# various.net
KiCad netlist of a schematic drawn in EAGLE
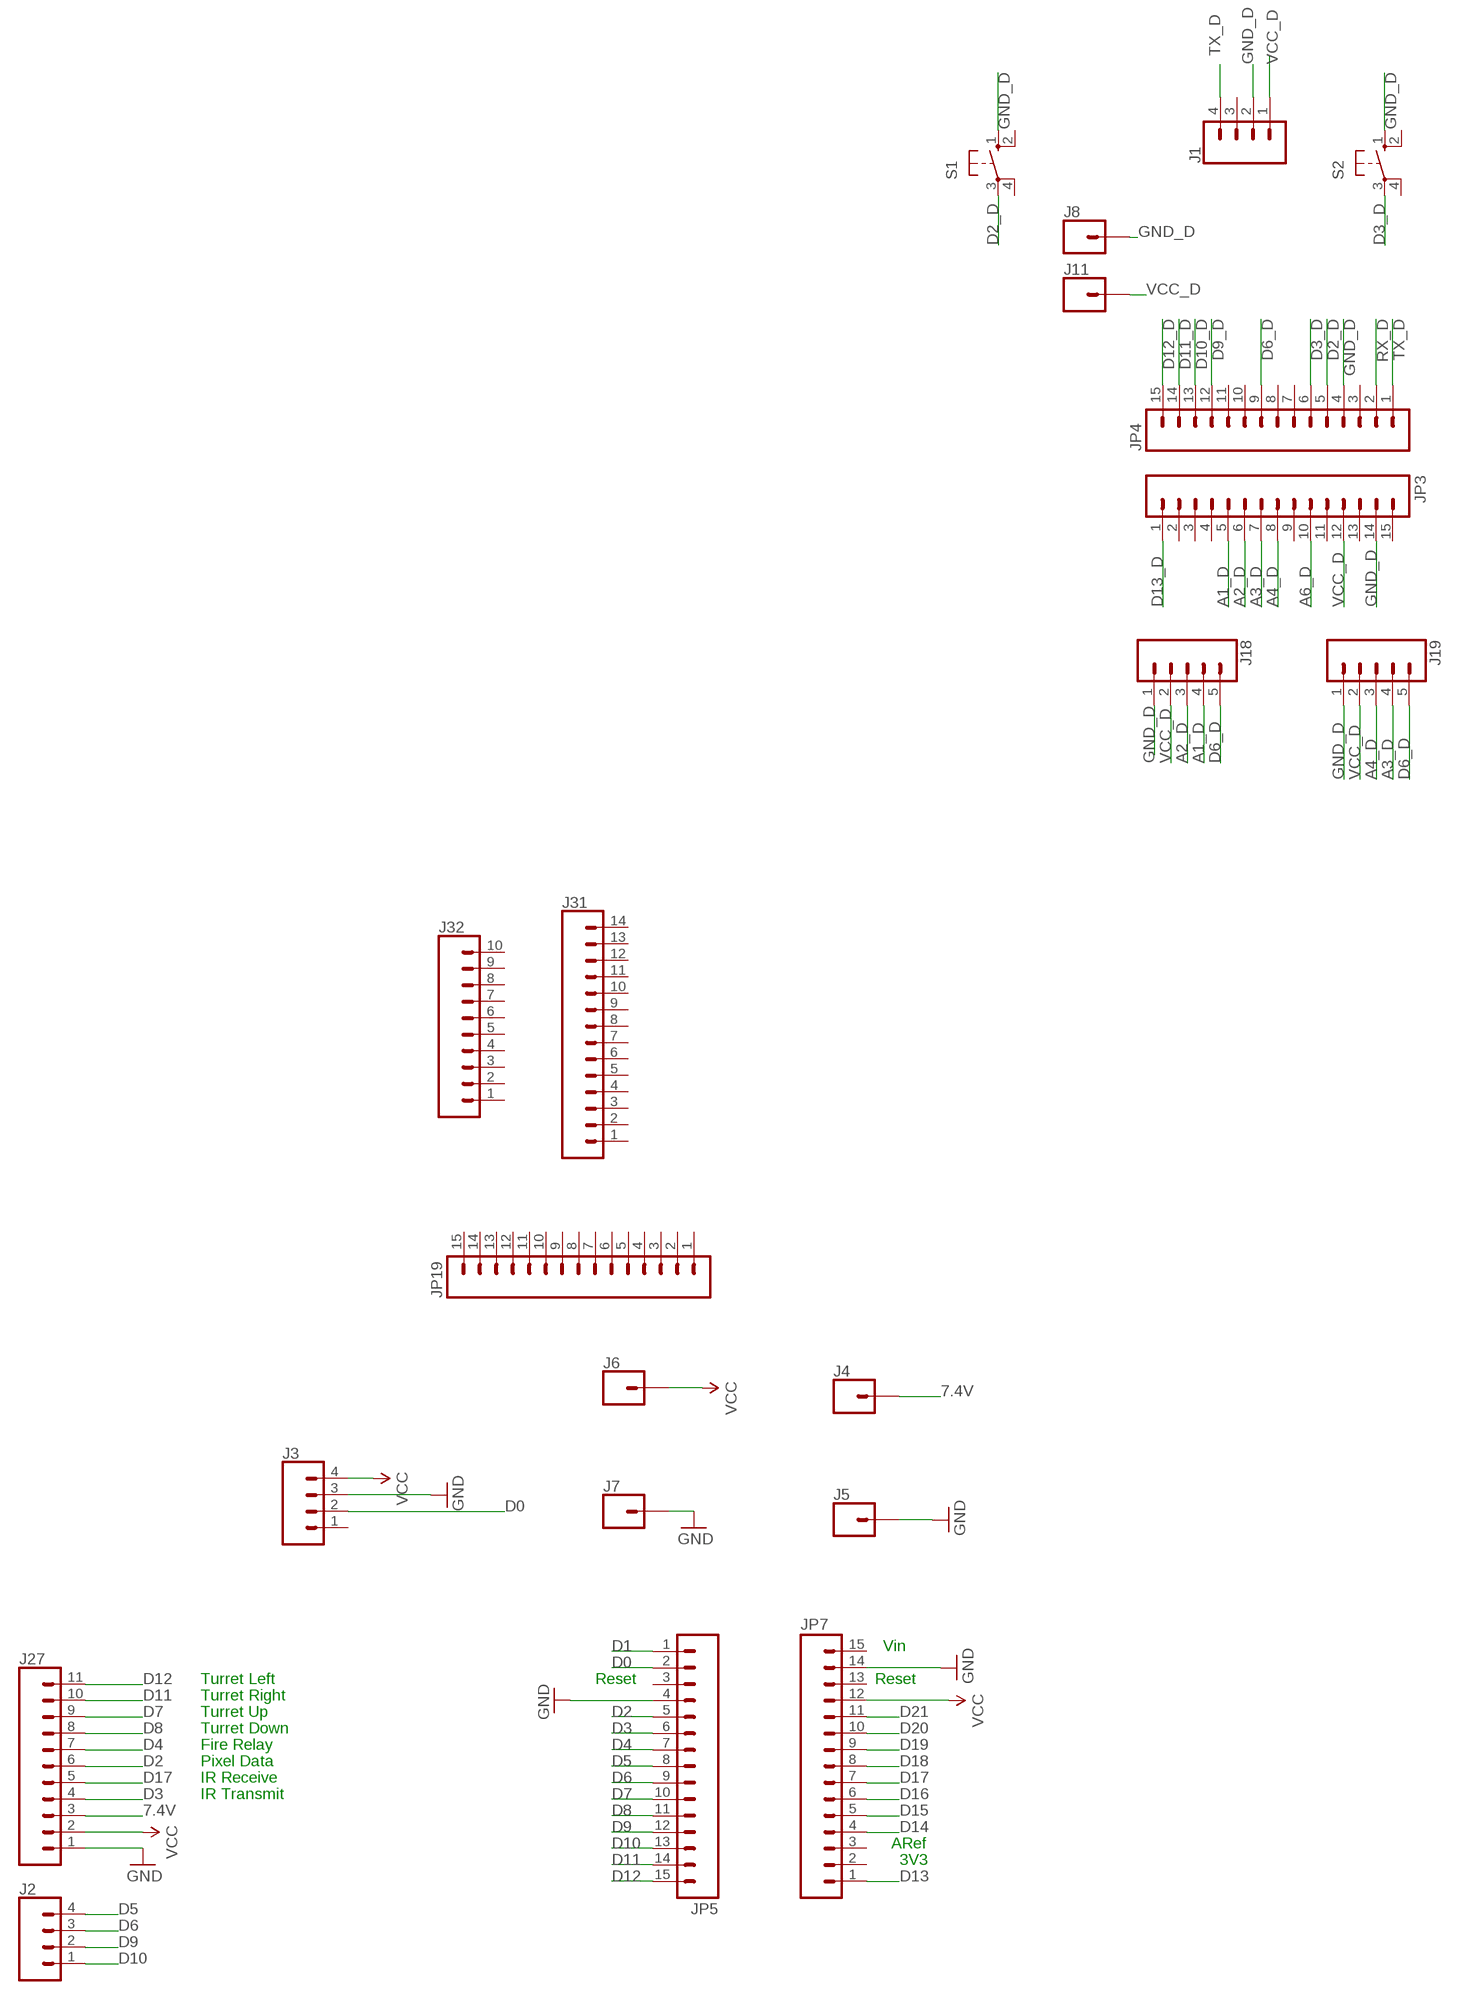
[diagram p0: schematic, sheet 1]

(export (version "E")
  (design (tool "Eeschema 10.0.6"))
  (components
    (comp (ref "J1")
      (value "CONN_04")
      (footprint "eagle-import:1X04")
      (libsource (lib "eagle-import") (part "SparkFun-Connectors_513_CONN_04"))
    )
    (comp (ref "J2")
      (value "CONN_04")
      (footprint "eagle-import:1X04")
      (libsource (lib "eagle-import") (part "CONN_04"))
    )
    (comp (ref "J3")
      (value "CONN_04")
      (footprint "eagle-import:1X04")
      (libsource (lib "eagle-import") (part "CONN_04"))
    )
    (comp (ref "J4")
      (value "CONN_01")
      (footprint "eagle-import:1X01")
      (libsource (lib "eagle-import") (part "CONN_01"))
    )
    (comp (ref "J5")
      (value "CONN_01")
      (footprint "eagle-import:1X01")
      (libsource (lib "eagle-import") (part "CONN_01"))
    )
    (comp (ref "J6")
      (value "CONN_01")
      (footprint "eagle-import:1X01")
      (libsource (lib "eagle-import") (part "CONN_01"))
    )
    (comp (ref "J7")
      (value "CONN_01")
      (footprint "eagle-import:1X01")
      (libsource (lib "eagle-import") (part "CONN_01"))
    )
    (comp (ref "J8")
      (value "CONN_01")
      (footprint "eagle-import:1X01")
      (libsource (lib "eagle-import") (part "CONN_01"))
    )
    (comp (ref "J11")
      (value "CONN_01")
      (footprint "eagle-import:1X01")
      (libsource (lib "eagle-import") (part "CONN_01"))
    )
    (comp (ref "J18")
      (value "CONN_05")
      (footprint "eagle-import:1X05")
      (libsource (lib "eagle-import") (part "CONN_05"))
    )
    (comp (ref "J19")
      (value "CONN_05")
      (footprint "eagle-import:1X05")
      (libsource (lib "eagle-import") (part "CONN_05"))
    )
    (comp (ref "J27")
      (value "CONN_11")
      (footprint "eagle-import:1X11")
      (libsource (lib "eagle-import") (part "CONN_11"))
    )
    (comp (ref "J31")
      (value "CONN_14")
      (footprint "eagle-import:1X14")
      (libsource (lib "eagle-import") (part "CONN_14"))
    )
    (comp (ref "J32")
      (value "CONN_10\"")
      (footprint "eagle-import:1X10")
      (libsource (lib "eagle-import") (part "CONN_10{dblquote}"))
    )
    (comp (ref "JP3")
      (value "M15")
      (footprint "eagle-import:1X15")
      (libsource (lib "eagle-import") (part "M15"))
    )
    (comp (ref "JP4")
      (value "M15")
      (footprint "eagle-import:1X15")
      (libsource (lib "eagle-import") (part "M15"))
    )
    (comp (ref "JP5")
      (value "M15")
      (footprint "eagle-import:1X15")
      (libsource (lib "eagle-import") (part "M15"))
    )
    (comp (ref "JP7")
      (value "M15")
      (footprint "eagle-import:1X15")
      (libsource (lib "eagle-import") (part "M15"))
    )
    (comp (ref "JP19")
      (value "M15")
      (footprint "eagle-import:1X15")
      (libsource (lib "eagle-import") (part "M15"))
    )
    (comp (ref "S1")
      (value "40-XX")
      (footprint "eagle-import:B3F-40XX")
      (fields (field (name "MF") "OMRON COMPONENTS USA") (field (name "MPN") "B3F-4000"))
      (libsource (lib "eagle-import") (part "40-XX"))
    )
    (comp (ref "S2")
      (value "40-XX")
      (footprint "eagle-import:B3F-40XX")
      (fields (field (name "MF") "OMRON COMPONENTS USA") (field (name "MPN") "B3F-4000"))
      (libsource (lib "eagle-import") (part "40-XX"))
    )
  )
  (nets
    (net (code "1") (name "/7.4V") (class "Default")
      (node (ref "J27") (pin "3") (pinfunction "3_3") (pintype "passive"))
      (node (ref "J4") (pin "1") (pinfunction "1_1") (pintype "passive"))
    )
    (net (code "2") (name "/A1_D") (class "Default")
      (node (ref "J18") (pin "4") (pinfunction "4_4") (pintype "passive"))
      (node (ref "JP3") (pin "5") (pinfunction "5_5") (pintype "passive"))
    )
    (net (code "3") (name "/A2_D") (class "Default")
      (node (ref "J18") (pin "3") (pinfunction "3_3") (pintype "passive"))
      (node (ref "JP3") (pin "6") (pinfunction "6_6") (pintype "passive"))
    )
    (net (code "4") (name "/A3_D") (class "Default")
      (node (ref "J19") (pin "4") (pinfunction "4_4") (pintype "passive"))
      (node (ref "JP3") (pin "7") (pinfunction "7_7") (pintype "passive"))
    )
    (net (code "5") (name "/A4_D") (class "Default")
      (node (ref "J19") (pin "3") (pinfunction "3_3") (pintype "passive"))
      (node (ref "JP3") (pin "8") (pinfunction "8_8") (pintype "passive"))
    )
    (net (code "6") (name "/A6_D") (class "Default")
      (node (ref "JP3") (pin "10") (pinfunction "10_10") (pintype "passive"))
    )
    (net (code "7") (name "/D0") (class "Default")
      (node (ref "J3") (pin "2") (pinfunction "2_2") (pintype "passive"))
      (node (ref "JP5") (pin "2") (pinfunction "2_2") (pintype "passive"))
    )
    (net (code "8") (name "/D1") (class "Default")
      (node (ref "JP5") (pin "1") (pinfunction "1_1") (pintype "passive"))
    )
    (net (code "9") (name "/D2") (class "Default")
      (node (ref "J27") (pin "6") (pinfunction "6_6") (pintype "passive"))
      (node (ref "JP5") (pin "5") (pinfunction "5_5") (pintype "passive"))
    )
    (net (code "10") (name "/D2_D") (class "Default")
      (node (ref "JP4") (pin "5") (pinfunction "5_5") (pintype "passive"))
      (node (ref "S1") (pin "3") (pinfunction "P_3") (pintype "passive"))
    )
    (net (code "11") (name "/D3") (class "Default")
      (node (ref "J27") (pin "4") (pinfunction "4_4") (pintype "passive"))
      (node (ref "JP5") (pin "6") (pinfunction "6_6") (pintype "passive"))
    )
    (net (code "12") (name "/D3_D") (class "Default")
      (node (ref "JP4") (pin "6") (pinfunction "6_6") (pintype "passive"))
      (node (ref "S2") (pin "3") (pinfunction "P_3") (pintype "passive"))
    )
    (net (code "13") (name "/D4") (class "Default")
      (node (ref "J27") (pin "7") (pinfunction "7_7") (pintype "passive"))
      (node (ref "JP5") (pin "7") (pinfunction "7_7") (pintype "passive"))
    )
    (net (code "14") (name "/D5") (class "Default")
      (node (ref "J2") (pin "4") (pinfunction "4_4") (pintype "passive"))
      (node (ref "JP5") (pin "8") (pinfunction "8_8") (pintype "passive"))
    )
    (net (code "15") (name "/D6") (class "Default")
      (node (ref "J2") (pin "3") (pinfunction "3_3") (pintype "passive"))
      (node (ref "JP5") (pin "9") (pinfunction "9_9") (pintype "passive"))
    )
    (net (code "16") (name "/D6_D") (class "Default")
      (node (ref "J18") (pin "5") (pinfunction "5_5") (pintype "passive"))
      (node (ref "J19") (pin "5") (pinfunction "5_5") (pintype "passive"))
      (node (ref "JP4") (pin "9") (pinfunction "9_9") (pintype "passive"))
    )
    (net (code "17") (name "/D7") (class "Default")
      (node (ref "J27") (pin "9") (pinfunction "9_9") (pintype "passive"))
      (node (ref "JP5") (pin "10") (pinfunction "10_10") (pintype "passive"))
    )
    (net (code "18") (name "/D8") (class "Default")
      (node (ref "J27") (pin "8") (pinfunction "8_8") (pintype "passive"))
      (node (ref "JP5") (pin "11") (pinfunction "11_11") (pintype "passive"))
    )
    (net (code "19") (name "/D9") (class "Default")
      (node (ref "J2") (pin "2") (pinfunction "2_2") (pintype "passive"))
      (node (ref "JP5") (pin "12") (pinfunction "12_12") (pintype "passive"))
    )
    (net (code "20") (name "/D9_D") (class "Default")
      (node (ref "JP4") (pin "12") (pinfunction "12_12") (pintype "passive"))
    )
    (net (code "21") (name "/D10") (class "Default")
      (node (ref "J2") (pin "1") (pinfunction "1_1") (pintype "passive"))
      (node (ref "JP5") (pin "13") (pinfunction "13_13") (pintype "passive"))
    )
    (net (code "22") (name "/D10_D") (class "Default")
      (node (ref "JP4") (pin "13") (pinfunction "13_13") (pintype "passive"))
    )
    (net (code "23") (name "/D11") (class "Default")
      (node (ref "J27") (pin "10") (pinfunction "10_10") (pintype "passive"))
      (node (ref "JP5") (pin "14") (pinfunction "14_14") (pintype "passive"))
    )
    (net (code "24") (name "/D11_D") (class "Default")
      (node (ref "JP4") (pin "14") (pinfunction "14_14") (pintype "passive"))
    )
    (net (code "25") (name "/D12") (class "Default")
      (node (ref "J27") (pin "11") (pinfunction "11_11") (pintype "passive"))
      (node (ref "JP5") (pin "15") (pinfunction "15_15") (pintype "passive"))
    )
    (net (code "26") (name "/D12_D") (class "Default")
      (node (ref "JP4") (pin "15") (pinfunction "15_15") (pintype "passive"))
    )
    (net (code "27") (name "/D13") (class "Default")
      (node (ref "JP7") (pin "1") (pinfunction "1_1") (pintype "passive"))
    )
    (net (code "28") (name "/D13_D") (class "Default")
      (node (ref "JP3") (pin "1") (pinfunction "1_1") (pintype "passive"))
    )
    (net (code "29") (name "/D14") (class "Default")
      (node (ref "JP7") (pin "4") (pinfunction "4_4") (pintype "passive"))
    )
    (net (code "30") (name "/D15") (class "Default")
      (node (ref "JP7") (pin "5") (pinfunction "5_5") (pintype "passive"))
    )
    (net (code "31") (name "/D16") (class "Default")
      (node (ref "JP7") (pin "6") (pinfunction "6_6") (pintype "passive"))
    )
    (net (code "32") (name "/D17") (class "Default")
      (node (ref "J27") (pin "5") (pinfunction "5_5") (pintype "passive"))
      (node (ref "JP7") (pin "7") (pinfunction "7_7") (pintype "passive"))
    )
    (net (code "33") (name "/D18") (class "Default")
      (node (ref "JP7") (pin "8") (pinfunction "8_8") (pintype "passive"))
    )
    (net (code "34") (name "/D19") (class "Default")
      (node (ref "JP7") (pin "9") (pinfunction "9_9") (pintype "passive"))
    )
    (net (code "35") (name "/D20") (class "Default")
      (node (ref "JP7") (pin "10") (pinfunction "10_10") (pintype "passive"))
    )
    (net (code "36") (name "/D21") (class "Default")
      (node (ref "JP7") (pin "11") (pinfunction "11_11") (pintype "passive"))
    )
    (net (code "37") (name "/GND_D") (class "Default")
      (node (ref "J1") (pin "2") (pinfunction "2_2") (pintype "passive"))
      (node (ref "J18") (pin "1") (pinfunction "1_1") (pintype "passive"))
      (node (ref "J19") (pin "1") (pinfunction "1_1") (pintype "passive"))
      (node (ref "J8") (pin "1") (pinfunction "1_1") (pintype "passive"))
      (node (ref "JP3") (pin "14") (pinfunction "14_14") (pintype "passive"))
      (node (ref "JP4") (pin "4") (pinfunction "4_4") (pintype "passive"))
      (node (ref "S1") (pin "1") (pinfunction "S_1") (pintype "passive"))
      (node (ref "S2") (pin "1") (pinfunction "S_1") (pintype "passive"))
    )
    (net (code "38") (name "/RX_D") (class "Default")
      (node (ref "JP4") (pin "2") (pinfunction "2_2") (pintype "passive"))
    )
    (net (code "39") (name "/TX_D") (class "Default")
      (node (ref "J1") (pin "4") (pinfunction "4_4") (pintype "passive"))
      (node (ref "JP4") (pin "1") (pinfunction "1_1") (pintype "passive"))
    )
    (net (code "40") (name "/VCC_D") (class "Default")
      (node (ref "J1") (pin "1") (pinfunction "1_1") (pintype "passive"))
      (node (ref "J11") (pin "1") (pinfunction "1_1") (pintype "passive"))
      (node (ref "J18") (pin "2") (pinfunction "2_2") (pintype "passive"))
      (node (ref "J19") (pin "2") (pinfunction "2_2") (pintype "passive"))
      (node (ref "JP3") (pin "12") (pinfunction "12_12") (pintype "passive"))
    )
    (net (code "41") (name "GND") (class "Default")
      (node (ref "J27") (pin "1") (pinfunction "1_1") (pintype "passive"))
      (node (ref "J3") (pin "3") (pinfunction "3_3") (pintype "passive"))
      (node (ref "J5") (pin "1") (pinfunction "1_1") (pintype "passive"))
      (node (ref "J7") (pin "1") (pinfunction "1_1") (pintype "passive"))
      (node (ref "JP5") (pin "4") (pinfunction "4_4") (pintype "passive"))
      (node (ref "JP7") (pin "14") (pinfunction "14_14") (pintype "passive"))
    )
    (net (code "42") (name "VCC") (class "Default")
      (node (ref "J27") (pin "2") (pinfunction "2_2") (pintype "passive"))
      (node (ref "J3") (pin "4") (pinfunction "4_4") (pintype "passive"))
      (node (ref "J6") (pin "1") (pinfunction "1_1") (pintype "passive"))
      (node (ref "JP7") (pin "12") (pinfunction "12_12") (pintype "passive"))
    )
    (net (code "43") (name "unconnected-(J1-Pad3)") (class "Default")
      (node (ref "J1") (pin "3") (pinfunction "3_3") (pintype "passive"))
    )
    (net (code "44") (name "unconnected-(J3-Pad1)") (class "Default")
      (node (ref "J3") (pin "1") (pinfunction "1_1") (pintype "passive"))
    )
    (net (code "45") (name "unconnected-(J31-Pad1)") (class "Default")
      (node (ref "J31") (pin "1") (pinfunction "1_1") (pintype "passive"))
    )
    (net (code "46") (name "unconnected-(J31-Pad2)") (class "Default")
      (node (ref "J31") (pin "2") (pinfunction "2_2") (pintype "passive"))
    )
    (net (code "47") (name "unconnected-(J31-Pad3)") (class "Default")
      (node (ref "J31") (pin "3") (pinfunction "3_3") (pintype "passive"))
    )
    (net (code "48") (name "unconnected-(J31-Pad4)") (class "Default")
      (node (ref "J31") (pin "4") (pinfunction "4_4") (pintype "passive"))
    )
    (net (code "49") (name "unconnected-(J31-Pad5)") (class "Default")
      (node (ref "J31") (pin "5") (pinfunction "5_5") (pintype "passive"))
    )
    (net (code "50") (name "unconnected-(J31-Pad6)") (class "Default")
      (node (ref "J31") (pin "6") (pinfunction "6_6") (pintype "passive"))
    )
    (net (code "51") (name "unconnected-(J31-Pad7)") (class "Default")
      (node (ref "J31") (pin "7") (pinfunction "7_7") (pintype "passive"))
    )
    (net (code "52") (name "unconnected-(J31-Pad8)") (class "Default")
      (node (ref "J31") (pin "8") (pinfunction "8_8") (pintype "passive"))
    )
    (net (code "53") (name "unconnected-(J31-Pad9)") (class "Default")
      (node (ref "J31") (pin "9") (pinfunction "9_9") (pintype "passive"))
    )
    (net (code "54") (name "unconnected-(J31-Pad10)") (class "Default")
      (node (ref "J31") (pin "10") (pinfunction "10_10") (pintype "passive"))
    )
    (net (code "55") (name "unconnected-(J31-Pad11)") (class "Default")
      (node (ref "J31") (pin "11") (pinfunction "11_11") (pintype "passive"))
    )
    (net (code "56") (name "unconnected-(J31-Pad12)") (class "Default")
      (node (ref "J31") (pin "12") (pinfunction "12_12") (pintype "passive"))
    )
    (net (code "57") (name "unconnected-(J31-Pad13)") (class "Default")
      (node (ref "J31") (pin "13") (pinfunction "13_13") (pintype "passive"))
    )
    (net (code "58") (name "unconnected-(J31-Pad14)") (class "Default")
      (node (ref "J31") (pin "14") (pinfunction "14_14") (pintype "passive"))
    )
    (net (code "59") (name "unconnected-(J32-Pad1)") (class "Default")
      (node (ref "J32") (pin "1") (pinfunction "1_1") (pintype "passive"))
    )
    (net (code "60") (name "unconnected-(J32-Pad2)") (class "Default")
      (node (ref "J32") (pin "2") (pinfunction "2_2") (pintype "passive"))
    )
    (net (code "61") (name "unconnected-(J32-Pad3)") (class "Default")
      (node (ref "J32") (pin "3") (pinfunction "3_3") (pintype "passive"))
    )
    (net (code "62") (name "unconnected-(J32-Pad4)") (class "Default")
      (node (ref "J32") (pin "4") (pinfunction "4_4") (pintype "passive"))
    )
    (net (code "63") (name "unconnected-(J32-Pad5)") (class "Default")
      (node (ref "J32") (pin "5") (pinfunction "5_5") (pintype "passive"))
    )
    (net (code "64") (name "unconnected-(J32-Pad6)") (class "Default")
      (node (ref "J32") (pin "6") (pinfunction "6_6") (pintype "passive"))
    )
    (net (code "65") (name "unconnected-(J32-Pad7)") (class "Default")
      (node (ref "J32") (pin "7") (pinfunction "7_7") (pintype "passive"))
    )
    (net (code "66") (name "unconnected-(J32-Pad8)") (class "Default")
      (node (ref "J32") (pin "8") (pinfunction "8_8") (pintype "passive"))
    )
    (net (code "67") (name "unconnected-(J32-Pad9)") (class "Default")
      (node (ref "J32") (pin "9") (pinfunction "9_9") (pintype "passive"))
    )
    (net (code "68") (name "unconnected-(J32-Pad10)") (class "Default")
      (node (ref "J32") (pin "10") (pinfunction "10_10") (pintype "passive"))
    )
    (net (code "69") (name "unconnected-(JP3-Pad2)") (class "Default")
      (node (ref "JP3") (pin "2") (pinfunction "2_2") (pintype "passive"))
    )
    (net (code "70") (name "unconnected-(JP3-Pad3)") (class "Default")
      (node (ref "JP3") (pin "3") (pinfunction "3_3") (pintype "passive"))
    )
    (net (code "71") (name "unconnected-(JP3-Pad4)") (class "Default")
      (node (ref "JP3") (pin "4") (pinfunction "4_4") (pintype "passive"))
    )
    (net (code "72") (name "unconnected-(JP3-Pad9)") (class "Default")
      (node (ref "JP3") (pin "9") (pinfunction "9_9") (pintype "passive"))
    )
    (net (code "73") (name "unconnected-(JP3-Pad11)") (class "Default")
      (node (ref "JP3") (pin "11") (pinfunction "11_11") (pintype "passive"))
    )
    (net (code "74") (name "unconnected-(JP3-Pad13)") (class "Default")
      (node (ref "JP3") (pin "13") (pinfunction "13_13") (pintype "passive"))
    )
    (net (code "75") (name "unconnected-(JP3-Pad15)") (class "Default")
      (node (ref "JP3") (pin "15") (pinfunction "15_15") (pintype "passive"))
    )
    (net (code "76") (name "unconnected-(JP4-Pad3)") (class "Default")
      (node (ref "JP4") (pin "3") (pinfunction "3_3") (pintype "passive"))
    )
    (net (code "77") (name "unconnected-(JP4-Pad7)") (class "Default")
      (node (ref "JP4") (pin "7") (pinfunction "7_7") (pintype "passive"))
    )
    (net (code "78") (name "unconnected-(JP4-Pad8)") (class "Default")
      (node (ref "JP4") (pin "8") (pinfunction "8_8") (pintype "passive"))
    )
    (net (code "79") (name "unconnected-(JP4-Pad10)") (class "Default")
      (node (ref "JP4") (pin "10") (pinfunction "10_10") (pintype "passive"))
    )
    (net (code "80") (name "unconnected-(JP4-Pad11)") (class "Default")
      (node (ref "JP4") (pin "11") (pinfunction "11_11") (pintype "passive"))
    )
    (net (code "81") (name "unconnected-(JP5-Pad3)") (class "Default")
      (node (ref "JP5") (pin "3") (pinfunction "3_3") (pintype "passive"))
    )
    (net (code "82") (name "unconnected-(JP7-Pad2)") (class "Default")
      (node (ref "JP7") (pin "2") (pinfunction "2_2") (pintype "passive"))
    )
    (net (code "83") (name "unconnected-(JP7-Pad3)") (class "Default")
      (node (ref "JP7") (pin "3") (pinfunction "3_3") (pintype "passive"))
    )
    (net (code "84") (name "unconnected-(JP7-Pad13)") (class "Default")
      (node (ref "JP7") (pin "13") (pinfunction "13_13") (pintype "passive"))
    )
    (net (code "85") (name "unconnected-(JP7-Pad15)") (class "Default")
      (node (ref "JP7") (pin "15") (pinfunction "15_15") (pintype "passive"))
    )
    (net (code "86") (name "unconnected-(JP19-Pad1)") (class "Default")
      (node (ref "JP19") (pin "1") (pinfunction "1_1") (pintype "passive"))
    )
    (net (code "87") (name "unconnected-(JP19-Pad2)") (class "Default")
      (node (ref "JP19") (pin "2") (pinfunction "2_2") (pintype "passive"))
    )
    (net (code "88") (name "unconnected-(JP19-Pad3)") (class "Default")
      (node (ref "JP19") (pin "3") (pinfunction "3_3") (pintype "passive"))
    )
    (net (code "89") (name "unconnected-(JP19-Pad4)") (class "Default")
      (node (ref "JP19") (pin "4") (pinfunction "4_4") (pintype "passive"))
    )
    (net (code "90") (name "unconnected-(JP19-Pad5)") (class "Default")
      (node (ref "JP19") (pin "5") (pinfunction "5_5") (pintype "passive"))
    )
    (net (code "91") (name "unconnected-(JP19-Pad6)") (class "Default")
      (node (ref "JP19") (pin "6") (pinfunction "6_6") (pintype "passive"))
    )
    (net (code "92") (name "unconnected-(JP19-Pad7)") (class "Default")
      (node (ref "JP19") (pin "7") (pinfunction "7_7") (pintype "passive"))
    )
    (net (code "93") (name "unconnected-(JP19-Pad8)") (class "Default")
      (node (ref "JP19") (pin "8") (pinfunction "8_8") (pintype "passive"))
    )
    (net (code "94") (name "unconnected-(JP19-Pad9)") (class "Default")
      (node (ref "JP19") (pin "9") (pinfunction "9_9") (pintype "passive"))
    )
    (net (code "95") (name "unconnected-(JP19-Pad10)") (class "Default")
      (node (ref "JP19") (pin "10") (pinfunction "10_10") (pintype "passive"))
    )
    (net (code "96") (name "unconnected-(JP19-Pad11)") (class "Default")
      (node (ref "JP19") (pin "11") (pinfunction "11_11") (pintype "passive"))
    )
    (net (code "97") (name "unconnected-(JP19-Pad12)") (class "Default")
      (node (ref "JP19") (pin "12") (pinfunction "12_12") (pintype "passive"))
    )
    (net (code "98") (name "unconnected-(JP19-Pad13)") (class "Default")
      (node (ref "JP19") (pin "13") (pinfunction "13_13") (pintype "passive"))
    )
    (net (code "99") (name "unconnected-(JP19-Pad14)") (class "Default")
      (node (ref "JP19") (pin "14") (pinfunction "14_14") (pintype "passive"))
    )
    (net (code "100") (name "unconnected-(JP19-Pad15)") (class "Default")
      (node (ref "JP19") (pin "15") (pinfunction "15_15") (pintype "passive"))
    )
    (net (code "101") (name "unconnected-(S1-P1-Pad4)") (class "Default")
      (node (ref "S1") (pin "4") (pinfunction "P1_4") (pintype "passive"))
    )
    (net (code "102") (name "unconnected-(S1-S1-Pad2)") (class "Default")
      (node (ref "S1") (pin "2") (pinfunction "S1_2") (pintype "passive"))
    )
    (net (code "103") (name "unconnected-(S2-P1-Pad4)") (class "Default")
      (node (ref "S2") (pin "4") (pinfunction "P1_4") (pintype "passive"))
    )
    (net (code "104") (name "unconnected-(S2-S1-Pad2)") (class "Default")
      (node (ref "S2") (pin "2") (pinfunction "S1_2") (pintype "passive"))
    )
  )
)
